# Hypnos_V2_2.net
KiCad netlist of a schematic drawn in EAGLE
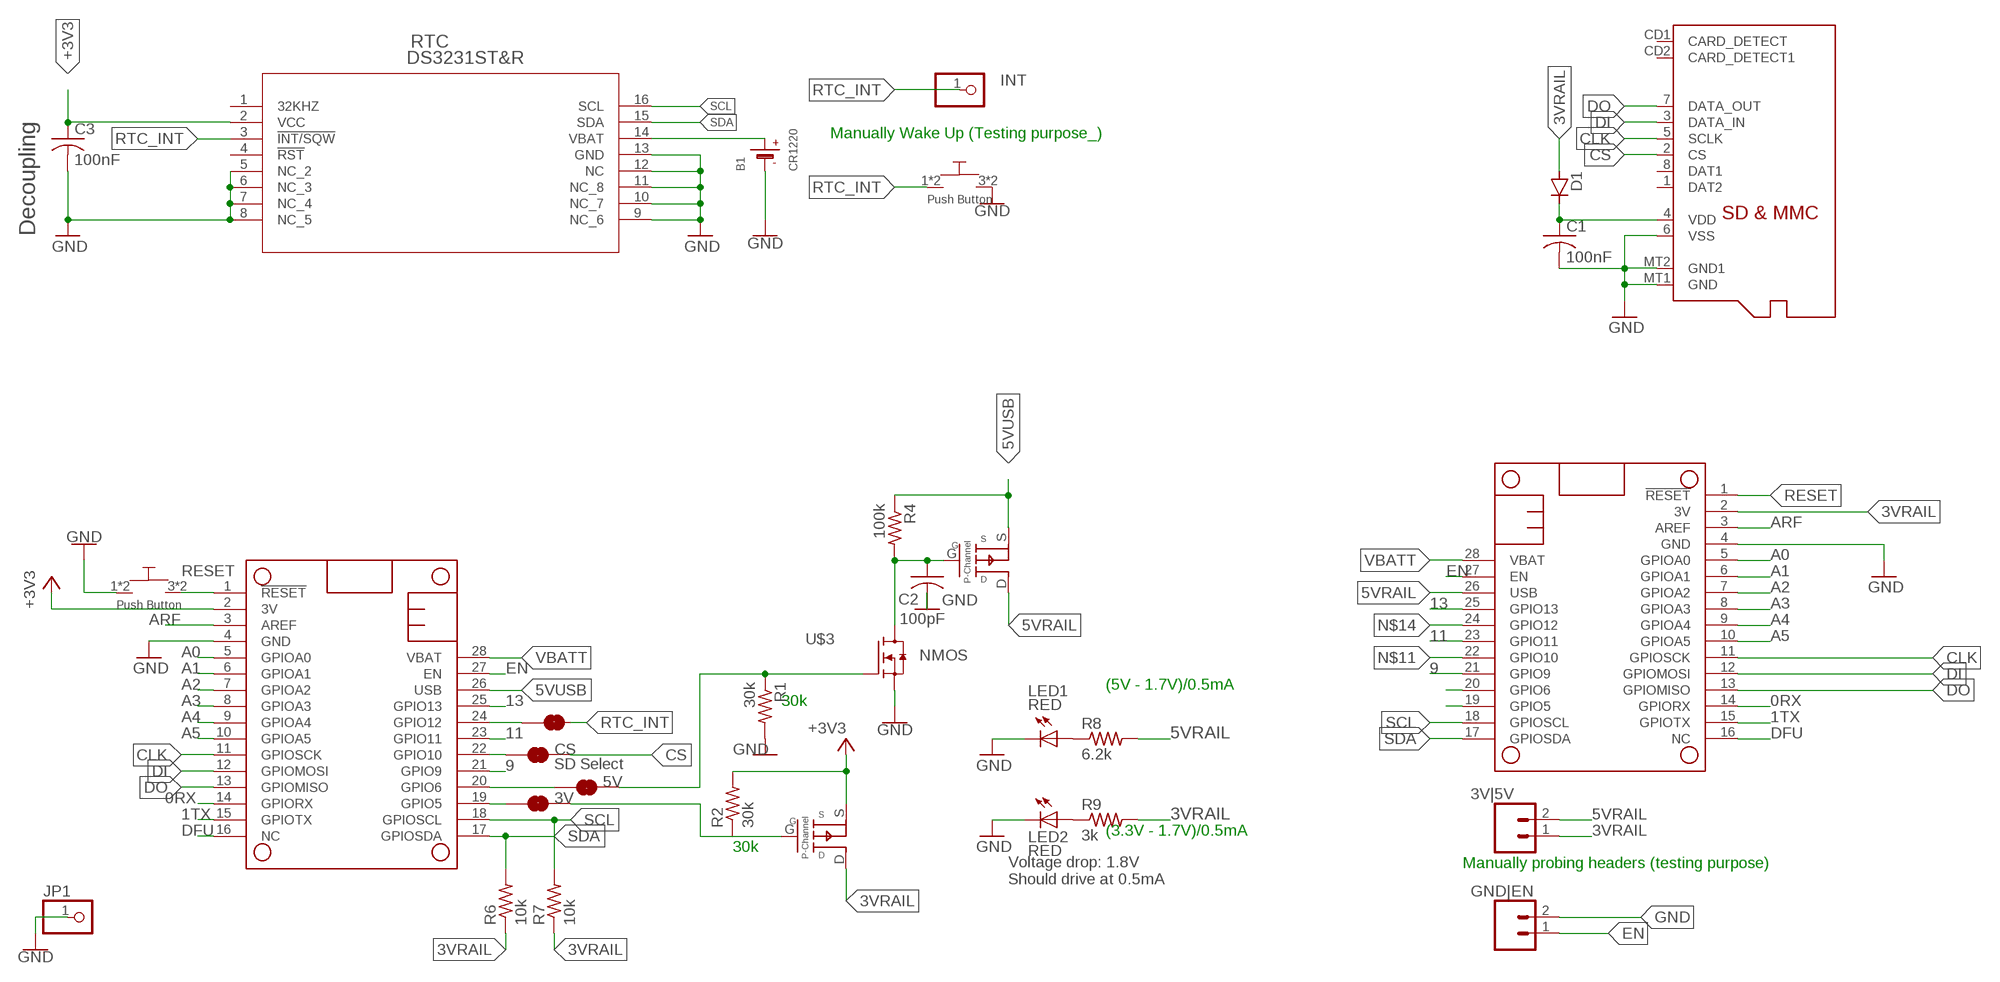
[diagram p0: schematic, sheet 1]

(export (version "E")
  (design (tool "Eeschema 10.0.6"))
  (components
    (comp (ref "3V")
      (value "JUMPER-SMT_2_NC_TRACE_SILK")
      (footprint "eagle-import:SMT-JUMPER_2_NC_TRACE_SILK")
      (libsource (lib "eagle-import") (part "JUMPER-SMT_2_NC_TRACE_SILK"))
    )
    (comp (ref "3V|5V")
      (value "CONN_021X02_NO_SILK")
      (footprint "eagle-import:1X02_NO_SILK")
      (libsource (lib "eagle-import") (part "CONN_021X02_NO_SILK"))
    )
    (comp (ref "5V")
      (value "JUMPER-SMT_2_NC_TRACE_SILK")
      (footprint "eagle-import:SMT-JUMPER_2_NC_TRACE_SILK")
      (libsource (lib "eagle-import") (part "JUMPER-SMT_2_NC_TRACE_SILK"))
    )
    (comp (ref "B1")
      (value "CR1220")
      (footprint "eagle-import:CR1220")
      (libsource (lib "eagle-import") (part "BATTERYCR1220_SMT"))
    )
    (comp (ref "C1")
      (value "100nF")
      (footprint "eagle-import:C1206")
      (libsource (lib "eagle-import") (part "C-USC1206"))
    )
    (comp (ref "C2")
      (value "100pF")
      (footprint "eagle-import:C0805")
      (libsource (lib "eagle-import") (part "C-USC0805"))
    )
    (comp (ref "C3")
      (value "100nF")
      (footprint "eagle-import:C1206")
      (libsource (lib "eagle-import") (part "C-USC1206"))
    )
    (comp (ref "CS")
      (value "SD Select")
      (footprint "eagle-import:SMT-JUMPER_2_NC_TRACE_SILK")
      (libsource (lib "eagle-import") (part "JUMPER-SMT_2_NC_TRACE_SILK"))
    )
    (comp (ref "D1")
      (value "D-SOD123")
      (footprint "eagle-import:SOD123")
      (libsource (lib "eagle-import") (part "D-SOD123"))
    )
    (comp (ref "GND|EN")
      (value "CONN_021X02_NO_SILK")
      (footprint "eagle-import:1X02_NO_SILK")
      (libsource (lib "eagle-import") (part "CONN_021X02_NO_SILK"))
    )
    (comp (ref "INT")
      (value "PINHD-1X1CB")
      (footprint "eagle-import:1X01-CLEANBIG")
      (libsource (lib "eagle-import") (part "PINHD-1X1CB"))
    )
    (comp (ref "JP1")
      (value "PINHD-1X1CB")
      (footprint "eagle-import:1X01-CLEANBIG")
      (libsource (lib "eagle-import") (part "PINHD-1X1CB"))
    )
    (comp (ref "LED1")
      (value "RED")
      (footprint "eagle-import:CHIPLED_0805")
      (libsource (lib "eagle-import") (part "LEDCHIPLED_0805"))
    )
    (comp (ref "LED2")
      (value "RED")
      (footprint "eagle-import:CHIPLED_0805")
      (libsource (lib "eagle-import") (part "LEDCHIPLED_0805"))
    )
    (comp (ref "MICROSD")
      (value "MICROSD")
      (footprint "eagle-import:MICROSD")
      (libsource (lib "eagle-import") (part "MICROSD"))
    )
    (comp (ref "MS1")
      (value "FEATHERWING")
      (footprint "eagle-import:FEATHERWING")
      (libsource (lib "eagle-import") (part "powerboard_FEATHERWING"))
    )
    (comp (ref "MS2")
      (value "FEATHERWING")
      (footprint "eagle-import:FEATHERWING")
      (libsource (lib "eagle-import") (part "FEATHERWING"))
    )
    (comp (ref "PMOS1")
      (value "SSM3J3228R")
      (footprint "eagle-import:SOT-23-3")
      (libsource (lib "eagle-import") (part "SSM3J3228R"))
    )
    (comp (ref "PMOS2")
      (value "SSM3J3228R")
      (footprint "eagle-import:SOT-23-3")
      (libsource (lib "eagle-import") (part "SSM3J3228R"))
    )
    (comp (ref "R1")
      (value "30k")
      (footprint "eagle-import:RES_1206")
      (fields
        (field (name "DIGIKEY_PART_NUMBER") "WSLP-.05TR-ND")
        (field (name "MANUFACTURER") "Vishay Dale")
        (field (name "MPN") "WSLP1206R0500FEA")
        (field (name "CREATED_BY") "PCBLayout.com")
      )
      (libsource (lib "eagle-import") (part "WSLP1206R0500FEA"))
    )
    (comp (ref "R2")
      (value "30k")
      (footprint "eagle-import:RES_1206")
      (fields
        (field (name "DIGIKEY_PART_NUMBER") "WSLP-.05TR-ND")
        (field (name "MANUFACTURER") "Vishay Dale")
        (field (name "MPN") "WSLP1206R0500FEA")
        (field (name "CREATED_BY") "PCBLayout.com")
      )
      (libsource (lib "eagle-import") (part "WSLP1206R0500FEA"))
    )
    (comp (ref "R4")
      (value "100k")
      (footprint "eagle-import:RES_1206")
      (fields
        (field (name "DIGIKEY_PART_NUMBER") "WSLP-.05TR-ND")
        (field (name "MANUFACTURER") "Vishay Dale")
        (field (name "MPN") "WSLP1206R0500FEA")
        (field (name "CREATED_BY") "PCBLayout.com")
      )
      (libsource (lib "eagle-import") (part "WSLP1206R0500FEA"))
    )
    (comp (ref "R6")
      (value "10k")
      (footprint "eagle-import:RES_1206")
      (fields
        (field (name "DIGIKEY_PART_NUMBER") "WSLP-.05TR-ND")
        (field (name "MANUFACTURER") "Vishay Dale")
        (field (name "MPN") "WSLP1206R0500FEA")
        (field (name "CREATED_BY") "PCBLayout.com")
      )
      (libsource (lib "eagle-import") (part "WSLP1206R0500FEA"))
    )
    (comp (ref "R7")
      (value "10k")
      (footprint "eagle-import:RES_1206")
      (fields
        (field (name "DIGIKEY_PART_NUMBER") "WSLP-.05TR-ND")
        (field (name "MANUFACTURER") "Vishay Dale")
        (field (name "MPN") "WSLP1206R0500FEA")
        (field (name "CREATED_BY") "PCBLayout.com")
      )
      (libsource (lib "eagle-import") (part "WSLP1206R0500FEA"))
    )
    (comp (ref "R8")
      (value "6.2k")
      (footprint "eagle-import:RES_1206")
      (fields
        (field (name "DIGIKEY_PART_NUMBER") "WSLP-.05TR-ND")
        (field (name "MANUFACTURER") "Vishay Dale")
        (field (name "MPN") "WSLP1206R0500FEA")
        (field (name "CREATED_BY") "PCBLayout.com")
      )
      (libsource (lib "eagle-import") (part "WSLP1206R0500FEA"))
    )
    (comp (ref "R9")
      (value "3k")
      (footprint "eagle-import:RES_1206")
      (fields
        (field (name "DIGIKEY_PART_NUMBER") "WSLP-.05TR-ND")
        (field (name "MANUFACTURER") "Vishay Dale")
        (field (name "MPN") "WSLP1206R0500FEA")
        (field (name "CREATED_BY") "PCBLayout.com")
      )
      (libsource (lib "eagle-import") (part "WSLP1206R0500FEA"))
    )
    (comp (ref "RTC")
      (value "DS3231ST&R")
      (footprint "eagle-import:21-0042B_16")
      (fields (field (name "MANUFACTURER_PART_NUMBER") "DS3231S#T&R"))
      (libsource (lib "eagle-import") (part "DS3231ST&R"))
    )
    (comp (ref "RTC_INT")
      (value "JUMPER-SMT_2_NC_TRACE_SILK")
      (footprint "eagle-import:SMT-JUMPER_2_NC_TRACE_SILK")
      (libsource (lib "eagle-import") (part "JUMPER-SMT_2_NC_TRACE_SILK"))
    )
    (comp (ref "U$1")
      (value "PUSH_BUTTON")
      (footprint "eagle-import:PUSHBUTTON_SMD")
      (libsource (lib "eagle-import") (part "PUSH_BUTTON"))
    )
    (comp (ref "U$2")
      (value "PUSH_BUTTON")
      (footprint "eagle-import:PUSHBUTTON_SMD")
      (libsource (lib "eagle-import") (part "PUSH_BUTTON"))
    )
    (comp (ref "U$3")
      (value "NMOS")
      (footprint "eagle-import:SOT23-S")
      (libsource (lib "eagle-import") (part "NMOS"))
    )
  )
  (nets
    (net (code "1") (name "+3V3") (class "Default")
      (node (ref "C3") (pin "1") (pinfunction "1_1") (pintype "passive"))
      (node (ref "MS2") (pin "2") (pinfunction "3V_2") (pintype "power_in"))
      (node (ref "PMOS2") (pin "S") (pinfunction "S_S") (pintype "bidirectional"))
      (node (ref "R2") (pin "2") (pinfunction "2_2") (pintype "passive"))
      (node (ref "RTC") (pin "2") (pinfunction "VCC_2") (pintype "power_in"))
    )
    (net (code "2") (name "/0RX") (class "Default")
      (node (ref "MS1") (pin "14") (pinfunction "GPIORX_14") (pintype "bidirectional"))
      (node (ref "MS2") (pin "14") (pinfunction "GPIORX_14") (pintype "bidirectional"))
    )
    (net (code "3") (name "/1TX") (class "Default")
      (node (ref "MS1") (pin "15") (pinfunction "GPIOTX_15") (pintype "bidirectional"))
      (node (ref "MS2") (pin "15") (pinfunction "GPIOTX_15") (pintype "bidirectional"))
    )
    (net (code "4") (name "/9") (class "Default")
      (node (ref "MS1") (pin "21") (pinfunction "GPIO9_21") (pintype "bidirectional"))
      (node (ref "MS2") (pin "21") (pinfunction "GPIO9_21") (pintype "bidirectional"))
    )
    (net (code "5") (name "/11") (class "Default")
      (node (ref "MS1") (pin "23") (pinfunction "GPIO11_23") (pintype "bidirectional"))
      (node (ref "MS2") (pin "23") (pinfunction "GPIO11_23") (pintype "bidirectional"))
    )
    (net (code "6") (name "/13") (class "Default")
      (node (ref "MS1") (pin "25") (pinfunction "GPIO13_25") (pintype "bidirectional"))
      (node (ref "MS2") (pin "25") (pinfunction "GPIO13_25") (pintype "bidirectional"))
    )
    (net (code "7") (name "/A0") (class "Default")
      (node (ref "MS1") (pin "5") (pinfunction "GPIOA0_5") (pintype "bidirectional"))
      (node (ref "MS2") (pin "5") (pinfunction "GPIOA0_5") (pintype "bidirectional"))
    )
    (net (code "8") (name "/A1") (class "Default")
      (node (ref "MS1") (pin "6") (pinfunction "GPIOA1_6") (pintype "bidirectional"))
      (node (ref "MS2") (pin "6") (pinfunction "GPIOA1_6") (pintype "bidirectional"))
    )
    (net (code "9") (name "/A2") (class "Default")
      (node (ref "MS1") (pin "7") (pinfunction "GPIOA2_7") (pintype "bidirectional"))
      (node (ref "MS2") (pin "7") (pinfunction "GPIOA2_7") (pintype "bidirectional"))
    )
    (net (code "10") (name "/A3") (class "Default")
      (node (ref "MS1") (pin "8") (pinfunction "GPIOA3_8") (pintype "bidirectional"))
      (node (ref "MS2") (pin "8") (pinfunction "GPIOA3_8") (pintype "bidirectional"))
    )
    (net (code "11") (name "/A4") (class "Default")
      (node (ref "MS1") (pin "9") (pinfunction "GPIOA4_9") (pintype "bidirectional"))
      (node (ref "MS2") (pin "9") (pinfunction "GPIOA4_9") (pintype "bidirectional"))
    )
    (net (code "12") (name "/A5") (class "Default")
      (node (ref "MS1") (pin "10") (pinfunction "GPIOA5_10") (pintype "bidirectional"))
      (node (ref "MS2") (pin "10") (pinfunction "GPIOA5_10") (pintype "bidirectional"))
    )
    (net (code "13") (name "/ARF") (class "Default")
      (node (ref "MS1") (pin "3") (pinfunction "AREF_3") (pintype "passive"))
      (node (ref "MS2") (pin "3") (pinfunction "AREF_3") (pintype "passive"))
    )
    (net (code "14") (name "/DFU") (class "Default")
      (node (ref "MS1") (pin "16") (pinfunction "NC_16") (pintype "passive"))
      (node (ref "MS2") (pin "16") (pinfunction "NC_16") (pintype "passive"))
    )
    (net (code "15") (name "3VRAIL") (class "Default")
      (node (ref "3V|5V") (pin "1") (pinfunction "1_1") (pintype "passive"))
      (node (ref "D1") (pin "2") (pinfunction "A_2") (pintype "passive"))
      (node (ref "MS1") (pin "2") (pinfunction "3V_2") (pintype "power_in"))
      (node (ref "PMOS2") (pin "D") (pinfunction "D_D") (pintype "bidirectional"))
      (node (ref "R6") (pin "1") (pinfunction "1_1") (pintype "passive"))
      (node (ref "R7") (pin "1") (pinfunction "1_1") (pintype "passive"))
      (node (ref "R9") (pin "2") (pinfunction "2_2") (pintype "passive"))
    )
    (net (code "16") (name "5VRAIL") (class "Default")
      (node (ref "3V|5V") (pin "2") (pinfunction "2_2") (pintype "passive"))
      (node (ref "MS1") (pin "26") (pinfunction "USB_26") (pintype "power_in"))
      (node (ref "PMOS1") (pin "D") (pinfunction "D_D") (pintype "bidirectional"))
      (node (ref "R8") (pin "2") (pinfunction "2_2") (pintype "passive"))
    )
    (net (code "17") (name "5VUSB") (class "Default")
      (node (ref "MS2") (pin "26") (pinfunction "USB_26") (pintype "power_in"))
      (node (ref "PMOS1") (pin "S") (pinfunction "S_S") (pintype "bidirectional"))
      (node (ref "R4") (pin "1") (pinfunction "1_1") (pintype "passive"))
    )
    (net (code "18") (name "CLK") (class "Default")
      (node (ref "MICROSD") (pin "5") (pinfunction "SCLK_5") (pintype "input"))
      (node (ref "MS1") (pin "11") (pinfunction "GPIOSCK_11") (pintype "bidirectional"))
      (node (ref "MS2") (pin "11") (pinfunction "GPIOSCK_11") (pintype "bidirectional"))
    )
    (net (code "19") (name "CS") (class "Default")
      (node (ref "CS") (pin "2") (pinfunction "2_2") (pintype "passive"))
      (node (ref "MICROSD") (pin "2") (pinfunction "CS_2") (pintype "input"))
    )
    (net (code "20") (name "DI") (class "Default")
      (node (ref "MICROSD") (pin "3") (pinfunction "DATA_IN_3") (pintype "input"))
      (node (ref "MS1") (pin "12") (pinfunction "GPIOMOSI_12") (pintype "bidirectional"))
      (node (ref "MS2") (pin "12") (pinfunction "GPIOMOSI_12") (pintype "bidirectional"))
    )
    (net (code "21") (name "DO") (class "Default")
      (node (ref "MICROSD") (pin "7") (pinfunction "DATA_OUT_7") (pintype "output"))
      (node (ref "MS1") (pin "13") (pinfunction "GPIOMISO_13") (pintype "bidirectional"))
      (node (ref "MS2") (pin "13") (pinfunction "GPIOMISO_13") (pintype "bidirectional"))
    )
    (net (code "22") (name "EN") (class "Default")
      (node (ref "GND|EN") (pin "1") (pinfunction "1_1") (pintype "passive"))
      (node (ref "MS1") (pin "27") (pinfunction "EN_27") (pintype "passive"))
      (node (ref "MS2") (pin "27") (pinfunction "EN_27") (pintype "passive"))
    )
    (net (code "23") (name "GND") (class "Default")
      (node (ref "B1") (pin "-") (pinfunction "-_-") (pintype "passive"))
      (node (ref "C1") (pin "2") (pinfunction "2_2") (pintype "passive"))
      (node (ref "C2") (pin "2") (pinfunction "2_2") (pintype "passive"))
      (node (ref "C3") (pin "2") (pinfunction "2_2") (pintype "passive"))
      (node (ref "GND|EN") (pin "2") (pinfunction "2_2") (pintype "passive"))
      (node (ref "JP1") (pin "1") (pinfunction "1_1") (pintype "passive"))
      (node (ref "LED1") (pin "C") (pinfunction "C_C") (pintype "passive"))
      (node (ref "LED2") (pin "C") (pinfunction "C_C") (pintype "passive"))
      (node (ref "MICROSD") (pin "6") (pinfunction "VSS_6") (pintype "power_in"))
      (node (ref "MICROSD") (pin "MT1") (pinfunction "GND_MT1") (pintype "power_in"))
      (node (ref "MICROSD") (pin "MT2") (pinfunction "GND1_MT2") (pintype "power_in"))
      (node (ref "MS1") (pin "4") (pinfunction "GND_4") (pintype "power_in"))
      (node (ref "MS2") (pin "4") (pinfunction "GND_4") (pintype "power_in"))
      (node (ref "R1") (pin "2") (pinfunction "2_2") (pintype "passive"))
      (node (ref "RTC") (pin "10") (pinfunction "NC_7_10") (pintype "passive"))
      (node (ref "RTC") (pin "11") (pinfunction "NC_8_11") (pintype "passive"))
      (node (ref "RTC") (pin "12") (pinfunction "NC_12") (pintype "passive"))
      (node (ref "RTC") (pin "13") (pinfunction "GND_13") (pintype "power_in"))
      (node (ref "RTC") (pin "5") (pinfunction "NC_2_5") (pintype "passive"))
      (node (ref "RTC") (pin "6") (pinfunction "NC_3_6") (pintype "passive"))
      (node (ref "RTC") (pin "7") (pinfunction "NC_4_7") (pintype "passive"))
      (node (ref "RTC") (pin "8") (pinfunction "NC_5_8") (pintype "passive"))
      (node (ref "RTC") (pin "9") (pinfunction "NC_6_9") (pintype "passive"))
      (node (ref "U$1") (pin "1") (pinfunction "P$1_1") (pintype "bidirectional"))
      (node (ref "U$1") (pin "2") (pinfunction "P$1_2") (pintype "bidirectional"))
      (node (ref "U$2") (pin "3") (pinfunction "P$2_3") (pintype "bidirectional"))
      (node (ref "U$2") (pin "4") (pinfunction "P$2_4") (pintype "bidirectional"))
      (node (ref "U$3") (pin "2") (pinfunction "S_2") (pintype "passive"))
    )
    (net (code "24") (name "N$11") (class "Default")
      (node (ref "CS") (pin "1") (pinfunction "1_1") (pintype "passive"))
      (node (ref "MS1") (pin "22") (pinfunction "GPIO10_22") (pintype "bidirectional"))
      (node (ref "MS2") (pin "22") (pinfunction "GPIO10_22") (pintype "bidirectional"))
    )
    (net (code "25") (name "N$14") (class "Default")
      (node (ref "MS1") (pin "24") (pinfunction "GPIO12_24") (pintype "bidirectional"))
      (node (ref "MS2") (pin "24") (pinfunction "GPIO12_24") (pintype "bidirectional"))
      (node (ref "RTC_INT") (pin "1") (pinfunction "1_1") (pintype "passive"))
    )
    (net (code "26") (name "Net-(3V-Pad2)") (class "Default")
      (node (ref "3V") (pin "2") (pinfunction "2_2") (pintype "passive"))
      (node (ref "PMOS2") (pin "G") (pinfunction "G_G") (pintype "bidirectional"))
      (node (ref "R2") (pin "1") (pinfunction "1_1") (pintype "passive"))
    )
    (net (code "27") (name "Net-(B1-+)") (class "Default")
      (node (ref "B1") (pin "+$1") (pinfunction "+_+$1") (pintype "passive"))
      (node (ref "RTC") (pin "14") (pinfunction "VBAT_14") (pintype "power_in"))
    )
    (net (code "28") (name "Net-(D1-C)") (class "Default")
      (node (ref "C1") (pin "1") (pinfunction "1_1") (pintype "passive"))
      (node (ref "D1") (pin "1") (pinfunction "C_1") (pintype "passive"))
      (node (ref "MICROSD") (pin "4") (pinfunction "VDD_4") (pintype "power_in"))
    )
    (net (code "29") (name "Net-(LED1-PadA)") (class "Default")
      (node (ref "LED1") (pin "A") (pinfunction "A_A") (pintype "passive"))
      (node (ref "R8") (pin "1") (pinfunction "1_1") (pintype "passive"))
    )
    (net (code "30") (name "Net-(LED2-PadA)") (class "Default")
      (node (ref "LED2") (pin "A") (pinfunction "A_A") (pintype "passive"))
      (node (ref "R9") (pin "1") (pinfunction "1_1") (pintype "passive"))
    )
    (net (code "31") (name "Net-(MS2-GPIO5)") (class "Default")
      (node (ref "3V") (pin "1") (pinfunction "1_1") (pintype "passive"))
      (node (ref "MS2") (pin "19") (pinfunction "GPIO5_19") (pintype "bidirectional"))
    )
    (net (code "32") (name "Net-(MS2-GPIO6)") (class "Default")
      (node (ref "5V") (pin "1") (pinfunction "1_1") (pintype "passive"))
      (node (ref "MS2") (pin "20") (pinfunction "GPIO6_20") (pintype "bidirectional"))
    )
    (net (code "33") (name "Net-(U$3-D)") (class "Default")
      (node (ref "C2") (pin "1") (pinfunction "1_1") (pintype "passive"))
      (node (ref "PMOS1") (pin "G") (pinfunction "G_G") (pintype "bidirectional"))
      (node (ref "R4") (pin "2") (pinfunction "2_2") (pintype "passive"))
      (node (ref "U$3") (pin "3") (pinfunction "D_3") (pintype "passive"))
    )
    (net (code "34") (name "Net-(U$3-G)") (class "Default")
      (node (ref "5V") (pin "2") (pinfunction "2_2") (pintype "passive"))
      (node (ref "R1") (pin "1") (pinfunction "1_1") (pintype "passive"))
      (node (ref "U$3") (pin "1") (pinfunction "G_1") (pintype "passive"))
    )
    (net (code "35") (name "RESET") (class "Default")
      (node (ref "MS1") (pin "1") (pinfunction "~{RESET}_1") (pintype "input"))
      (node (ref "MS2") (pin "1") (pinfunction "~{RESET}_1") (pintype "input"))
      (node (ref "U$1") (pin "3") (pinfunction "P$2_3") (pintype "bidirectional"))
      (node (ref "U$1") (pin "4") (pinfunction "P$2_4") (pintype "bidirectional"))
    )
    (net (code "36") (name "RTC_INT") (class "Default")
      (node (ref "INT") (pin "1") (pinfunction "1_1") (pintype "passive"))
      (node (ref "RTC") (pin "3") (pinfunction "~{INT/SQW}_3") (pintype "passive"))
      (node (ref "RTC_INT") (pin "2") (pinfunction "2_2") (pintype "passive"))
      (node (ref "U$2") (pin "1") (pinfunction "P$1_1") (pintype "bidirectional"))
      (node (ref "U$2") (pin "2") (pinfunction "P$1_2") (pintype "bidirectional"))
    )
    (net (code "37") (name "SCL") (class "Default")
      (node (ref "MS1") (pin "18") (pinfunction "GPIOSCL_18") (pintype "bidirectional"))
      (node (ref "MS2") (pin "18") (pinfunction "GPIOSCL_18") (pintype "bidirectional"))
      (node (ref "R7") (pin "2") (pinfunction "2_2") (pintype "passive"))
      (node (ref "RTC") (pin "16") (pinfunction "SCL_16") (pintype "passive"))
    )
    (net (code "38") (name "SDA") (class "Default")
      (node (ref "MS1") (pin "17") (pinfunction "GPIOSDA_17") (pintype "bidirectional"))
      (node (ref "MS2") (pin "17") (pinfunction "GPIOSDA_17") (pintype "bidirectional"))
      (node (ref "R6") (pin "2") (pinfunction "2_2") (pintype "passive"))
      (node (ref "RTC") (pin "15") (pinfunction "SDA_15") (pintype "passive"))
    )
    (net (code "39") (name "VBATT") (class "Default")
      (node (ref "MS1") (pin "28") (pinfunction "VBAT_28") (pintype "power_in"))
      (node (ref "MS2") (pin "28") (pinfunction "VBAT_28") (pintype "power_in"))
    )
    (net (code "40") (name "unconnected-(MICROSD-CARD_DETECT-PadCD1)") (class "Default")
      (node (ref "MICROSD") (pin "CD1") (pinfunction "CARD_DETECT_CD1") (pintype "passive"))
    )
    (net (code "41") (name "unconnected-(MICROSD-CARD_DETECT1-PadCD2)") (class "Default")
      (node (ref "MICROSD") (pin "CD2") (pinfunction "CARD_DETECT1_CD2") (pintype "passive"))
    )
    (net (code "42") (name "unconnected-(MICROSD-DAT1-Pad8)") (class "Default")
      (node (ref "MICROSD") (pin "8") (pinfunction "DAT1_8") (pintype "bidirectional"))
    )
    (net (code "43") (name "unconnected-(MICROSD-DAT2-Pad1)") (class "Default")
      (node (ref "MICROSD") (pin "1") (pinfunction "DAT2_1") (pintype "bidirectional"))
    )
    (net (code "44") (name "unconnected-(MS1-GPIO5-Pad19)") (class "Default")
      (node (ref "MS1") (pin "19") (pinfunction "GPIO5_19") (pintype "bidirectional"))
    )
    (net (code "45") (name "unconnected-(MS1-GPIO6-Pad20)") (class "Default")
      (node (ref "MS1") (pin "20") (pinfunction "GPIO6_20") (pintype "bidirectional"))
    )
    (net (code "46") (name "unconnected-(RTC-32KHZ-Pad1)") (class "Default")
      (node (ref "RTC") (pin "1") (pinfunction "32KHZ_1") (pintype "passive"))
    )
    (net (code "47") (name "unconnected-(RTC-~{RST}-Pad4)") (class "Default")
      (node (ref "RTC") (pin "4") (pinfunction "~{RST}_4") (pintype "passive"))
    )
  )
)
